# Candunio.net
KiCad netlist of a schematic drawn in Altium Designer
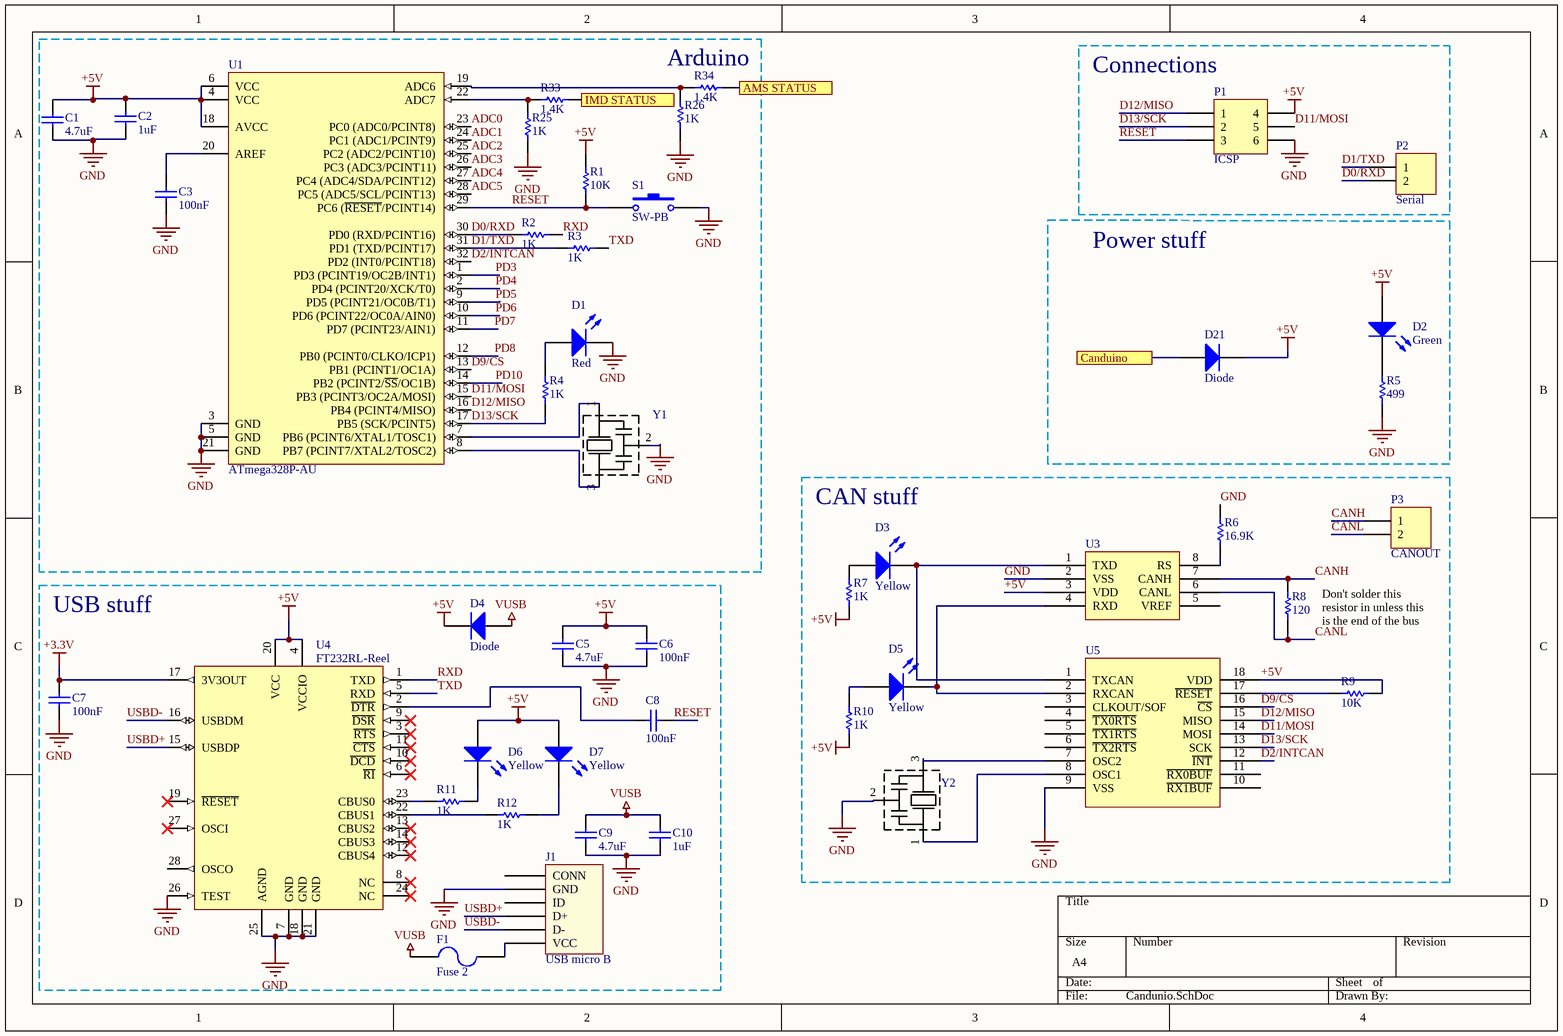
[diagram p0: Candunio.SchDoc]

(export (version "E")
  (design (tool "Eeschema 10.0.6"))
  (components
    (comp (ref "C1")
      (value "4.7uF")
      (footprint "CAPC3216X170N")
      (description "Capacitor (Semiconductor SIM Model)")
      (fields
        (field (name "MANUFACTURER") "Murata")
        (field (name "MANUFACTURER PART NUMBER") "GRM31MR71H105KA88L")
        (field (name "PUBLISHER") "Altium Limited")
      )
      (libsource (lib "PowerDistLib") (part "Cap Semi"))
    )
    (comp (ref "C2")
      (value "1uF")
      (footprint "CAPC3216X170N")
      (description "Capacitor (Semiconductor SIM Model)")
      (fields
        (field (name "MANUFACTURER") "Murata")
        (field (name "MANUFACTURER PART NUMBER") "GRM31MR71H105KA88L")
        (field (name "PUBLISHER") "Altium Limited")
      )
      (libsource (lib "PowerDistLib") (part "Cap Semi"))
    )
    (comp (ref "C3")
      (value "100nF")
      (footprint "CAPC3216X170N")
      (description "Capacitor (Semiconductor SIM Model)")
      (fields
        (field (name "MANUFACTURER") "Murata")
        (field (name "MANUFACTURER PART NUMBER") "GRM31MR71H105KA88L")
        (field (name "PUBLISHER") "Altium Limited")
      )
      (libsource (lib "PowerDistLib") (part "Cap Semi"))
    )
    (comp (ref "C5")
      (value "4.7uF")
      (footprint "PowerDistLib:CAPC3216X170N")
      (description "Capacitor (Semiconductor SIM Model)")
      (fields
        (field (name "MANUFACTURER") "Murata")
        (field (name "MANUFACTURER PART NUMBER") "GRM31MR71H105KA88L")
        (field (name "PUBLISHER") "Altium Limited")
      )
      (libsource (lib "PowerDistLib") (part "Cap Semi"))
    )
    (comp (ref "C6")
      (value "100nF")
      (footprint "CAPC3216X170N")
      (description "Capacitor (Semiconductor SIM Model)")
      (fields
        (field (name "MANUFACTURER") "Murata")
        (field (name "MANUFACTURER PART NUMBER") "GRM31MR71H105KA88L")
        (field (name "PUBLISHER") "Altium Limited")
      )
      (libsource (lib "PowerDistLib") (part "Cap Semi"))
    )
    (comp (ref "C7")
      (value "100nF")
      (footprint "PowerDistLib:CAPC3216X170N")
      (description "Capacitor (Semiconductor SIM Model)")
      (fields
        (field (name "MANUFACTURER") "Murata")
        (field (name "MANUFACTURER PART NUMBER") "GRM31MR71H105KA88L")
        (field (name "PUBLISHER") "Altium Limited")
      )
      (libsource (lib "PowerDistLib") (part "Cap Semi"))
    )
    (comp (ref "C8")
      (value "100nF")
      (footprint "CAPC3216X170N")
      (description "Capacitor (Semiconductor SIM Model)")
      (fields
        (field (name "MANUFACTURER") "Murata")
        (field (name "MANUFACTURER PART NUMBER") "GRM31MR71H105KA88L")
        (field (name "PUBLISHER") "Altium Limited")
      )
      (libsource (lib "PowerDistLib") (part "Cap Semi"))
    )
    (comp (ref "C9")
      (value "4.7uF")
      (footprint "CAPC3216X170N")
      (description "Capacitor (Semiconductor SIM Model)")
      (fields
        (field (name "MANUFACTURER") "Murata")
        (field (name "MANUFACTURER PART NUMBER") "GRM31MR71H105KA88L")
        (field (name "PUBLISHER") "Altium Limited")
      )
      (libsource (lib "PowerDistLib") (part "Cap Semi"))
    )
    (comp (ref "C10")
      (value "1uF")
      (footprint "CAPC3216X170N")
      (description "Capacitor (Semiconductor SIM Model)")
      (fields
        (field (name "MANUFACTURER") "Murata")
        (field (name "MANUFACTURER PART NUMBER") "GRM31MR71H105KA88L")
        (field (name "PUBLISHER") "Altium Limited")
      )
      (libsource (lib "PowerDistLib") (part "Cap Semi"))
    )
    (comp (ref "D1")
      (value "Red")
      (footprint "LEDC3216X120NRED")
      (description "Typical RED, GREEN, YELLOW, AMBER GaAs LED")
      (fields
        (field (name "MANUFACTURER") "Broadcom Avago")
        (field (name "MANUFACTURER PART NUMBER") "HSMY-C150")
        (field (name "PUBLISHER") "Altium Limited")
      )
      (libsource (lib "Miscellaneous Devices") (part "LED2"))
    )
    (comp (ref "D2")
      (value "Green")
      (footprint "LEDC3216X120NGRN")
      (description "Typical RED, GREEN, YELLOW, AMBER GaAs LED")
      (fields
        (field (name "MANUFACTURER") "Broadcom Avago")
        (field (name "MANUFACTURER PART NUMBER") "HSMG-C150")
        (field (name "PUBLISHER") "Altium Limited")
      )
      (libsource (lib "Miscellaneous Devices") (part "LED2"))
    )
    (comp (ref "D3")
      (value "Yellow")
      (footprint "LEDC3216X120NYEL")
      (description "Typical RED, GREEN, YELLOW, AMBER GaAs LED")
      (fields
        (field (name "MANUFACTURER") "Broadcom Avago")
        (field (name "MANUFACTURER PART NUMBER") "HSMY-C150")
        (field (name "PUBLISHER") "Altium Limited")
      )
      (libsource (lib "Miscellaneous Devices") (part "LED2"))
    )
    (comp (ref "D4")
      (value "Diode")
      (footprint "PowerDistLib:DO-220AA")
      (description "Default Diode")
      (fields (field (name "PUBLISHER") "Altium Limited"))
      (libsource (lib "PowerDistLib") (part "Diode"))
    )
    (comp (ref "D5")
      (value "Yellow")
      (footprint "LEDC3216X120NYEL")
      (description "Typical RED, GREEN, YELLOW, AMBER GaAs LED")
      (fields
        (field (name "MANUFACTURER") "Broadcom Avago")
        (field (name "MANUFACTURER PART NUMBER") "HSMY-C150")
        (field (name "PUBLISHER") "Altium Limited")
      )
      (libsource (lib "Miscellaneous Devices") (part "LED2"))
    )
    (comp (ref "D6")
      (value "Yellow")
      (footprint "LEDC3216X120NYEL")
      (description "Typical RED, GREEN, YELLOW, AMBER GaAs LED")
      (fields
        (field (name "MANUFACTURER") "Broadcom Avago")
        (field (name "MANUFACTURER PART NUMBER") "HSMY-C150")
        (field (name "PUBLISHER") "Altium Limited")
      )
      (libsource (lib "Miscellaneous Devices") (part "LED2"))
    )
    (comp (ref "D7")
      (value "Yellow")
      (footprint "LEDC3216X120NYEL")
      (description "Typical RED, GREEN, YELLOW, AMBER GaAs LED")
      (fields
        (field (name "MANUFACTURER") "Broadcom Avago")
        (field (name "MANUFACTURER PART NUMBER") "HSMY-C150")
        (field (name "PUBLISHER") "Altium Limited")
      )
      (libsource (lib "Miscellaneous Devices") (part "LED2"))
    )
    (comp (ref "D21")
      (value "Diode")
      (footprint "PowerDistLib:DO-220AA")
      (description "Default Diode")
      (fields (field (name "PUBLISHER") "Altium Limited"))
      (libsource (lib "PowerDistLib") (part "Diode"))
    )
    (comp (ref "F1")
      (value "Fuse 2")
      (footprint "1812")
      (description "Fuse")
      (fields
        (field (name "PART NUMBER") "MF-MSMF050-2")
        (field (name "MANUFACTURER") "Bourns")
        (field (name "PUBLISHER") "Altium Limited")
      )
      (libsource (lib "Miscellaneous Devices") (part "Fuse 2"))
    )
    (comp (ref "J1")
      (value "USB micro B")
      (footprint "1050170001")
      (description "CONN SM TH USB MICRO MODIFIED FOR DRILL")
      (fields (field (name "PART NUMBER") "WM1399CT-ND"))
      (libsource (lib "electronpowered") (part "1050170001"))
    )
    (comp (ref "P1")
      (value "ICSP")
      (footprint "Pin Header 2x3 TH Pitch 2.54mm")
      (description "Header, 3-Pin, Dual row")
      (fields (field (name "PUBLISHER") "Altium Limited"))
      (libsource (lib "PowerDistLib") (part "Header 3X2A"))
    )
    (comp (ref "P2")
      (value "Serial")
      (footprint "Pin Header 1x2 TH Pitch 2.54mm")
      (description "Header, 2-Pin")
      (fields (field (name "PUBLISHER") "Altium Limited"))
      (libsource (lib "Miscellaneous Connectors") (part "Header 2"))
    )
    (comp (ref "P3")
      (value "CANOUT")
      (description "Header, 2-Pin")
      (fields (field (name "PUBLISHER") "Altium Limited"))
      (libsource (lib "Miscellaneous Connectors") (part "Header 2"))
    )
    (comp (ref "R1")
      (value "10K")
      (footprint "RESC3216X60N")
      (description "Resistor")
      (fields
        (field (name "MANUFACTURER") "Stackpole Electronics")
        (field (name "MANUFACTURER PART NUMBER") "RNCP1206FTD1K00")
      )
      (libsource (lib "Miscellaneous Devices") (part "Res1"))
    )
    (comp (ref "R2")
      (value "1K")
      (footprint "RESC3216X60N")
      (description "Resistor")
      (fields
        (field (name "MANUFACTURER") "Stackpole Electronics")
        (field (name "MANUFACTURER PART NUMBER") "RNCP1206FTD1K00")
      )
      (libsource (lib "Miscellaneous Devices") (part "Res1"))
    )
    (comp (ref "R3")
      (value "1K")
      (footprint "RESC3216X60N")
      (description "Resistor")
      (fields
        (field (name "MANUFACTURER") "Stackpole Electronics")
        (field (name "MANUFACTURER PART NUMBER") "RNCP1206FTD1K00")
      )
      (libsource (lib "Miscellaneous Devices") (part "Res1"))
    )
    (comp (ref "R4")
      (value "1K")
      (footprint "RESC3216X60N")
      (description "Resistor")
      (fields
        (field (name "MANUFACTURER") "Stackpole Electronics")
        (field (name "MANUFACTURER PART NUMBER") "RNCP1206FTD1K00")
      )
      (libsource (lib "Miscellaneous Devices") (part "Res1"))
    )
    (comp (ref "R5")
      (value "499")
      (footprint "RESC3216X60N")
      (description "Resistor")
      (fields
        (field (name "MANUFACTURER") "Stackpole Electronics")
        (field (name "MANUFACTURER PART NUMBER") "RMCF1206FT499RCT-ND")
      )
      (libsource (lib "Miscellaneous Devices") (part "Res1"))
    )
    (comp (ref "R6")
      (value "16.9K")
      (footprint "RESC3216X60N")
      (description "Resistor")
      (fields
        (field (name "MANUFACTURER") "TE Connectivity Holsworthy")
        (field (name "MANUFACTURER PART NUMBER") "CRGH1206F16K9")
      )
      (libsource (lib "Miscellaneous Devices") (part "Res1"))
    )
    (comp (ref "R7")
      (value "1K")
      (footprint "RESC3216X60N")
      (description "Resistor")
      (fields
        (field (name "MANUFACTURER") "Stackpole Electronics")
        (field (name "MANUFACTURER PART NUMBER") "RNCP1206FTD1K00")
      )
      (libsource (lib "Miscellaneous Devices") (part "Res1"))
    )
    (comp (ref "R8")
      (value "120")
      (footprint "RESC3216X60N")
      (description "Resistor")
      (fields
        (field (name "MANUFACTURER") "Vishay")
        (field (name "MANUFACTURER PART NUMBER") "CRCW1206120RFKEAHP")
      )
      (libsource (lib "Miscellaneous Devices") (part "Res1"))
    )
    (comp (ref "R9")
      (value "10K")
      (footprint "RESC3216X60N")
      (description "Resistor")
      (fields
        (field (name "MANUFACTURER") "Stackpole Electronics")
        (field (name "MANUFACTURER PART NUMBER") "RNCP1206FTD10K0")
      )
      (libsource (lib "Miscellaneous Devices") (part "Res1"))
    )
    (comp (ref "R10")
      (value "1K")
      (footprint "RESC3216X60N")
      (description "Resistor")
      (fields
        (field (name "MANUFACTURER") "Stackpole Electronics")
        (field (name "MANUFACTURER PART NUMBER") "RNCP1206FTD1K00")
      )
      (libsource (lib "Miscellaneous Devices") (part "Res1"))
    )
    (comp (ref "R11")
      (value "1K")
      (footprint "RESC3216X60N")
      (description "Resistor")
      (fields
        (field (name "MANUFACTURER") "Stackpole Electronics")
        (field (name "MANUFACTURER PART NUMBER") "RNCP1206FTD1K00")
      )
      (libsource (lib "Miscellaneous Devices") (part "Res1"))
    )
    (comp (ref "R12")
      (value "1K")
      (footprint "RESC3216X60N")
      (description "Resistor")
      (fields
        (field (name "MANUFACTURER") "Stackpole Electronics")
        (field (name "MANUFACTURER PART NUMBER") "RNCP1206FTD1K00")
      )
      (libsource (lib "Miscellaneous Devices") (part "Res1"))
    )
    (comp (ref "R25")
      (value "1K")
      (footprint "RESC3216X60N")
      (description "Resistor")
      (fields
        (field (name "MANUFACTURER") "Stackpole Electronics")
        (field (name "MANUFACTURER PART NUMBER") "RNCP1206FTD1K00")
      )
      (libsource (lib "Power Distribution Unit 2019") (part "Res1"))
    )
    (comp (ref "R26")
      (value "1K")
      (footprint "RESC3216X60N")
      (description "Resistor")
      (fields
        (field (name "MANUFACTURER") "Stackpole Electronics")
        (field (name "MANUFACTURER PART NUMBER") "RNCP1206FTD1K00")
      )
      (libsource (lib "Power Distribution Unit 2019") (part "Res1"))
    )
    (comp (ref "R33")
      (value "1.4K")
      (footprint "RESC3216X60N")
      (description "Resistor")
      (fields
        (field (name "MANUFACTURER") "Stackpole Electronics")
        (field (name "MANUFACTURER PART NUMBER") "RNCP1206FTD1K00")
      )
      (libsource (lib "Power Distribution Unit 2019") (part "Res1"))
    )
    (comp (ref "R34")
      (value "1.4K")
      (footprint "RESC3216X60N")
      (description "Resistor")
      (fields
        (field (name "MANUFACTURER") "Stackpole Electronics")
        (field (name "MANUFACTURER PART NUMBER") "RNCP1206FTD1K00")
      )
      (libsource (lib "Power Distribution Unit 2019") (part "Res1"))
    )
    (comp (ref "S1")
      (value "SW-PB")
      (footprint "SMDswitch_1206")
      (description "Switch")
      (fields
        (field (name "MANUFACTURER") "ITT C&K")
        (field (name "MANUFACTURER PART NUMBER") "KXT331LHS")
        (field (name "PUBLISHER") "Altium Limited")
      )
      (libsource (lib "Miscellaneous Devices") (part "SW-PB"))
    )
    (comp (ref "U1")
      (value "ATmega328P-AU")
      (footprint "QFP80P900X900X120-32N")
      (fields (field (name "PUBLISHER") "Altium Limited"))
      (libsource (lib "Atmel Microcontroller 8-Bit megaAVR") (part "ATmega328P-AU"))
    )
    (comp (ref "U3")
      (value "MCP2551-E/SN")
      (footprint "SOIC127P600X175-8N")
      (description "SOIC")
      (libsource (lib "AMSComponents") (part "MCP2551-E/SN"))
    )
    (comp (ref "U4")
      (value "FT232RL-Reel")
      (footprint "PowerDist1:SOP65P780X200-28N")
      (description "USB UART Asynchronous Serial Data Transfer Chip, SSOP-28, Tape and Reel")
      (fields
        (field (name "MANUFACTURER") "FTDI")
        (field (name "MANUFACTURER PART NUMBER") "FT232RL-REEL")
        (field (name "PUBLISHER") "Altium Limited")
      )
      (libsource (lib "FTDI Communication UART") (part "FT232RL-Reel"))
    )
    (comp (ref "U5")
      (value "MCP2515-E/ST")
      (footprint "SOIC127P1030X265-18N")
      (description "SOIC")
      (libsource (lib "AMSComponents") (part "MCP2515-E/ST"))
    )
    (comp (ref "Y1")
      (value "CSTCE16M0V53-R0")
      (footprint "CSTCE_G")
      (fields
        (field (name "MANUFACTURER") "Murata")
        (field (name "MANUFACTURER PART NUMBER") "CSTCE16M0V53C-R0")
        (field (name "TOLERANCE") "0.5%")
      )
      (libsource (lib "AMSComponents") (part "CSTCE16M0V53-R0"))
    )
    (comp (ref "Y2")
      (value "CSTCE16M0V53-R0")
      (footprint "CSTCE_G")
      (fields
        (field (name "MANUFACTURER") "Murata")
        (field (name "MANUFACTURER PART NUMBER") "CSTCE16M0V53C-R0")
        (field (name "TOLERANCE") "0.5%")
      )
      (libsource (lib "AMSComponents") (part "CSTCE16M0V53-R0"))
    )
  )
  (nets
    (net (code "1") (name "+3.3V") (class "Default")
      (node (ref "C7") (pin "2") (pinfunction "2_2") (pintype "passive"))
      (node (ref "U4") (pin "17") (pinfunction "3V3OUT_17") (pintype "output"))
    )
    (net (code "2") (name "+5V") (class "Default")
      (node (ref "C1") (pin "1") (pinfunction "1_1") (pintype "passive"))
      (node (ref "C2") (pin "2") (pinfunction "2_2") (pintype "passive"))
      (node (ref "C5") (pin "2") (pinfunction "2_2") (pintype "passive"))
      (node (ref "C6") (pin "2") (pinfunction "2_2") (pintype "passive"))
      (node (ref "D2") (pin "1") (pinfunction "A_1") (pintype "passive"))
      (node (ref "D21") (pin "2") (pinfunction "K_2") (pintype "passive"))
      (node (ref "D4") (pin "2") (pinfunction "K_2") (pintype "passive"))
      (node (ref "D6") (pin "1") (pinfunction "A_1") (pintype "passive"))
      (node (ref "D7") (pin "1") (pinfunction "A_1") (pintype "passive"))
      (node (ref "P1") (pin "4") (pinfunction "4_4") (pintype "passive"))
      (node (ref "R1") (pin "1") (pinfunction "1_1") (pintype "passive"))
      (node (ref "R10") (pin "2") (pinfunction "2_2") (pintype "passive"))
      (node (ref "R7") (pin "1") (pinfunction "1_1") (pintype "passive"))
      (node (ref "R9") (pin "2") (pinfunction "2_2") (pintype "passive"))
      (node (ref "U1") (pin "18") (pinfunction "AVCC_18") (pintype "power_in"))
      (node (ref "U1") (pin "4") (pinfunction "VCC_4") (pintype "power_in"))
      (node (ref "U1") (pin "6") (pinfunction "VCC_6") (pintype "power_in"))
      (node (ref "U3") (pin "3") (pinfunction "VDD_3") (pintype "passive"))
      (node (ref "U4") (pin "20") (pinfunction "VCC_20") (pintype "power_in"))
      (node (ref "U4") (pin "4") (pinfunction "VCCIO_4") (pintype "power_in"))
      (node (ref "U5") (pin "18") (pinfunction "VDD_18") (pintype "passive"))
    )
    (net (code "3") (name "/ADC0") (class "Default")
      (node (ref "U1") (pin "23") (pinfunction "PC0_(ADC0/PCINT8)_23") (pintype "bidirectional"))
    )
    (net (code "4") (name "/ADC1") (class "Default")
      (node (ref "U1") (pin "24") (pinfunction "PC1_(ADC1/PCINT9)_24") (pintype "bidirectional"))
    )
    (net (code "5") (name "/ADC2") (class "Default")
      (node (ref "U1") (pin "25") (pinfunction "PC2_(ADC2/PCINT10)_25") (pintype "bidirectional"))
    )
    (net (code "6") (name "/ADC3") (class "Default")
      (node (ref "U1") (pin "26") (pinfunction "PC3_(ADC3/PCINT11)_26") (pintype "bidirectional"))
    )
    (net (code "7") (name "/ADC4") (class "Default")
      (node (ref "U1") (pin "27") (pinfunction "PC4_(ADC4/SDA/PCINT12)_27") (pintype "bidirectional"))
    )
    (net (code "8") (name "/ADC5") (class "Default")
      (node (ref "U1") (pin "28") (pinfunction "PC5_(ADC5/SCL/PCINT13)_28") (pintype "bidirectional"))
    )
    (net (code "9") (name "/AMS STATUS") (class "Default")
      (node (ref "R34") (pin "2") (pinfunction "2_2") (pintype "passive"))
    )
    (net (code "10") (name "/CANH") (class "Default")
      (node (ref "P3") (pin "1") (pinfunction "1_1") (pintype "passive"))
      (node (ref "R8") (pin "1") (pinfunction "1_1") (pintype "passive"))
      (node (ref "U3") (pin "7") (pinfunction "CANH_7") (pintype "passive"))
    )
    (net (code "11") (name "/CANL") (class "Default")
      (node (ref "P3") (pin "2") (pinfunction "2_2") (pintype "passive"))
      (node (ref "R8") (pin "2") (pinfunction "2_2") (pintype "passive"))
      (node (ref "U3") (pin "6") (pinfunction "CANL_6") (pintype "passive"))
    )
    (net (code "12") (name "/Canduino") (class "Default")
      (node (ref "D21") (pin "1") (pinfunction "A_1") (pintype "passive"))
    )
    (net (code "13") (name "/D0{slash}RXD") (class "Default")
      (node (ref "P2") (pin "2") (pinfunction "2_2") (pintype "passive"))
      (node (ref "R2") (pin "1") (pinfunction "1_1") (pintype "passive"))
      (node (ref "U1") (pin "30") (pinfunction "PD0_(RXD/PCINT16)_30") (pintype "bidirectional"))
    )
    (net (code "14") (name "/D1{slash}TXD") (class "Default")
      (node (ref "P2") (pin "1") (pinfunction "1_1") (pintype "passive"))
      (node (ref "R3") (pin "1") (pinfunction "1_1") (pintype "passive"))
      (node (ref "U1") (pin "31") (pinfunction "PD1_(TXD/PCINT17)_31") (pintype "bidirectional"))
    )
    (net (code "15") (name "/D2{slash}INTCAN") (class "Default")
      (node (ref "U1") (pin "32") (pinfunction "PD2_(INT0/PCINT18)_32") (pintype "bidirectional"))
      (node (ref "U5") (pin "12") (pinfunction "~{INT}_12") (pintype "passive"))
    )
    (net (code "16") (name "/D9{slash}CS") (class "Default")
      (node (ref "U1") (pin "13") (pinfunction "PB1_(PCINT1/OC1A)_13") (pintype "bidirectional"))
      (node (ref "U5") (pin "16") (pinfunction "~{CS}_16") (pintype "passive"))
    )
    (net (code "17") (name "/D11{slash}MOSI") (class "Default")
      (node (ref "P1") (pin "5") (pinfunction "5_5") (pintype "passive"))
      (node (ref "U1") (pin "15") (pinfunction "PB3_(PCINT3/OC2A/MOSI)_15") (pintype "bidirectional"))
      (node (ref "U5") (pin "14") (pinfunction "MOSI_14") (pintype "passive"))
    )
    (net (code "18") (name "/D12{slash}MISO") (class "Default")
      (node (ref "P1") (pin "1") (pinfunction "1_1") (pintype "passive"))
      (node (ref "U1") (pin "16") (pinfunction "PB4_(PCINT4/MISO)_16") (pintype "bidirectional"))
      (node (ref "U5") (pin "15") (pinfunction "MISO_15") (pintype "passive"))
    )
    (net (code "19") (name "/D13{slash}SCK") (class "Default")
      (node (ref "P1") (pin "2") (pinfunction "2_2") (pintype "passive"))
      (node (ref "R4") (pin "2") (pinfunction "2_2") (pintype "passive"))
      (node (ref "U1") (pin "17") (pinfunction "PB5_(SCK/PCINT5)_17") (pintype "bidirectional"))
      (node (ref "U5") (pin "13") (pinfunction "SCK_13") (pintype "passive"))
    )
    (net (code "20") (name "/IMD STATUS") (class "Default")
      (node (ref "R33") (pin "2") (pinfunction "2_2") (pintype "passive"))
    )
    (net (code "21") (name "/PD3") (class "Default")
      (node (ref "U1") (pin "1") (pinfunction "PD3_(PCINT19/OC2B/INT1)_1") (pintype "bidirectional"))
    )
    (net (code "22") (name "/PD4") (class "Default")
      (node (ref "U1") (pin "2") (pinfunction "PD4_(PCINT20/XCK/T0)_2") (pintype "bidirectional"))
    )
    (net (code "23") (name "/PD5") (class "Default")
      (node (ref "U1") (pin "9") (pinfunction "PD5_(PCINT21/OC0B/T1)_9") (pintype "bidirectional"))
    )
    (net (code "24") (name "/PD6") (class "Default")
      (node (ref "U1") (pin "10") (pinfunction "PD6_(PCINT22/OC0A/AIN0)_10") (pintype "bidirectional"))
    )
    (net (code "25") (name "/PD7") (class "Default")
      (node (ref "U1") (pin "11") (pinfunction "PD7_(PCINT23/AIN1)_11") (pintype "bidirectional"))
    )
    (net (code "26") (name "/PD8") (class "Default")
      (node (ref "U1") (pin "12") (pinfunction "PB0_(PCINT0/CLKO/ICP1)_12") (pintype "bidirectional"))
    )
    (net (code "27") (name "/PD10") (class "Default")
      (node (ref "U1") (pin "14") (pinfunction "PB2_(PCINT2/~{SS}/OC1B)_14") (pintype "bidirectional"))
    )
    (net (code "28") (name "/RESET") (class "Default")
      (node (ref "C8") (pin "2") (pinfunction "2_2") (pintype "passive"))
      (node (ref "P1") (pin "3") (pinfunction "3_3") (pintype "passive"))
      (node (ref "R1") (pin "2") (pinfunction "2_2") (pintype "passive"))
      (node (ref "S1") (pin "1") (pinfunction "1_1") (pintype "passive"))
      (node (ref "U1") (pin "29") (pinfunction "PC6_(~{RESET}/PCINT14)_29") (pintype "bidirectional"))
    )
    (net (code "29") (name "/RXD") (class "Default")
      (node (ref "R2") (pin "2") (pinfunction "2_2") (pintype "passive"))
      (node (ref "U4") (pin "1") (pinfunction "TXD_1") (pintype "output"))
    )
    (net (code "30") (name "/TXD") (class "Default")
      (node (ref "R3") (pin "2") (pinfunction "2_2") (pintype "passive"))
      (node (ref "U4") (pin "5") (pinfunction "RXD_5") (pintype "input"))
    )
    (net (code "31") (name "/USBD+") (class "Default")
      (node (ref "J1") (pin "3") (pinfunction "D+_3") (pintype "passive"))
      (node (ref "U4") (pin "15") (pinfunction "USBDP_15") (pintype "bidirectional"))
    )
    (net (code "32") (name "/USBD-") (class "Default")
      (node (ref "J1") (pin "2") (pinfunction "D-_2") (pintype "passive"))
      (node (ref "U4") (pin "16") (pinfunction "USBDM_16") (pintype "bidirectional"))
    )
    (net (code "33") (name "GND") (class "Default")
      (node (ref "C1") (pin "2") (pinfunction "2_2") (pintype "passive"))
      (node (ref "C10") (pin "1") (pinfunction "1_1") (pintype "passive"))
      (node (ref "C2") (pin "1") (pinfunction "1_1") (pintype "passive"))
      (node (ref "C3") (pin "1") (pinfunction "1_1") (pintype "passive"))
      (node (ref "C5") (pin "1") (pinfunction "1_1") (pintype "passive"))
      (node (ref "C6") (pin "1") (pinfunction "1_1") (pintype "passive"))
      (node (ref "C7") (pin "1") (pinfunction "1_1") (pintype "passive"))
      (node (ref "C9") (pin "1") (pinfunction "1_1") (pintype "passive"))
      (node (ref "D1") (pin "2") (pinfunction "K_2") (pintype "passive"))
      (node (ref "J1") (pin "5") (pinfunction "GND_5") (pintype "passive"))
      (node (ref "P1") (pin "6") (pinfunction "6_6") (pintype "passive"))
      (node (ref "R25") (pin "1") (pinfunction "1_1") (pintype "passive"))
      (node (ref "R26") (pin "1") (pinfunction "1_1") (pintype "passive"))
      (node (ref "R5") (pin "2") (pinfunction "2_2") (pintype "passive"))
      (node (ref "R6") (pin "1") (pinfunction "1_1") (pintype "passive"))
      (node (ref "S1") (pin "2") (pinfunction "2_2") (pintype "passive"))
      (node (ref "U1") (pin "21") (pinfunction "GND_21") (pintype "power_in"))
      (node (ref "U1") (pin "3") (pinfunction "GND_3") (pintype "power_in"))
      (node (ref "U1") (pin "5") (pinfunction "GND_5") (pintype "power_in"))
      (node (ref "U3") (pin "2") (pinfunction "VSS_2") (pintype "passive"))
      (node (ref "U4") (pin "18") (pinfunction "GND_18") (pintype "power_in"))
      (node (ref "U4") (pin "21") (pinfunction "GND_21") (pintype "power_in"))
      (node (ref "U4") (pin "25") (pinfunction "AGND_25") (pintype "power_in"))
      (node (ref "U4") (pin "26") (pinfunction "TEST_26") (pintype "input"))
      (node (ref "U4") (pin "7") (pinfunction "GND_7") (pintype "power_in"))
      (node (ref "U5") (pin "9") (pinfunction "VSS_9") (pintype "passive"))
      (node (ref "Y1") (pin "2") (pinfunction "2_2") (pintype "passive"))
      (node (ref "Y2") (pin "2") (pinfunction "2_2") (pintype "passive"))
    )
    (net (code "34") (name "Net-(D1-A)") (class "Default")
      (node (ref "D1") (pin "1") (pinfunction "A_1") (pintype "passive"))
      (node (ref "R4") (pin "1") (pinfunction "1_1") (pintype "passive"))
    )
    (net (code "35") (name "Net-(D2-K)") (class "Default")
      (node (ref "D2") (pin "2") (pinfunction "K_2") (pintype "passive"))
      (node (ref "R5") (pin "1") (pinfunction "1_1") (pintype "passive"))
    )
    (net (code "36") (name "Net-(D3-A)") (class "Default")
      (node (ref "D3") (pin "1") (pinfunction "A_1") (pintype "passive"))
      (node (ref "R7") (pin "2") (pinfunction "2_2") (pintype "passive"))
    )
    (net (code "37") (name "Net-(D3-K)") (class "Default")
      (node (ref "D3") (pin "2") (pinfunction "K_2") (pintype "passive"))
      (node (ref "U3") (pin "1") (pinfunction "TXD_1") (pintype "passive"))
      (node (ref "U5") (pin "1") (pinfunction "TXCAN_1") (pintype "passive"))
    )
    (net (code "38") (name "Net-(D5-A)") (class "Default")
      (node (ref "D5") (pin "1") (pinfunction "A_1") (pintype "passive"))
      (node (ref "R10") (pin "1") (pinfunction "1_1") (pintype "passive"))
    )
    (net (code "39") (name "Net-(D5-K)") (class "Default")
      (node (ref "D5") (pin "2") (pinfunction "K_2") (pintype "passive"))
      (node (ref "U3") (pin "4") (pinfunction "RXD_4") (pintype "passive"))
      (node (ref "U5") (pin "2") (pinfunction "RXCAN_2") (pintype "passive"))
    )
    (net (code "40") (name "Net-(D6-K)") (class "Default")
      (node (ref "D6") (pin "2") (pinfunction "K_2") (pintype "passive"))
      (node (ref "R11") (pin "2") (pinfunction "2_2") (pintype "passive"))
    )
    (net (code "41") (name "Net-(D7-K)") (class "Default")
      (node (ref "D7") (pin "2") (pinfunction "K_2") (pintype "passive"))
      (node (ref "R12") (pin "2") (pinfunction "2_2") (pintype "passive"))
    )
    (net (code "42") (name "Net-(J1-VCC)") (class "Default")
      (node (ref "F1") (pin "2") (pinfunction "2_2") (pintype "passive"))
      (node (ref "J1") (pin "1") (pinfunction "VCC_1") (pintype "passive"))
    )
    (net (code "43") (name "Net-(U1-ADC6)") (class "Default")
      (node (ref "R26") (pin "2") (pinfunction "2_2") (pintype "passive"))
      (node (ref "R34") (pin "1") (pinfunction "1_1") (pintype "passive"))
      (node (ref "U1") (pin "19") (pinfunction "ADC6_19") (pintype "input"))
    )
    (net (code "44") (name "Net-(U1-ADC7)") (class "Default")
      (node (ref "R25") (pin "2") (pinfunction "2_2") (pintype "passive"))
      (node (ref "R33") (pin "1") (pinfunction "1_1") (pintype "passive"))
      (node (ref "U1") (pin "22") (pinfunction "ADC7_22") (pintype "input"))
    )
    (net (code "45") (name "Net-(U1-AREF)") (class "Default")
      (node (ref "C3") (pin "2") (pinfunction "2_2") (pintype "passive"))
      (node (ref "U1") (pin "20") (pinfunction "AREF_20") (pintype "passive"))
    )
    (net (code "46") (name "Net-(U1-PB6_(PCINT6{slash}XTAL1{slash}TOSC1))") (class "Default")
      (node (ref "U1") (pin "7") (pinfunction "PB6_(PCINT6/XTAL1/TOSC1)_7") (pintype "bidirectional"))
      (node (ref "Y1") (pin "1") (pinfunction "1_1") (pintype "passive"))
    )
    (net (code "47") (name "Net-(U1-PB7_(PCINT7{slash}XTAL2{slash}TOSC2))") (class "Default")
      (node (ref "U1") (pin "8") (pinfunction "PB7_(PCINT7/XTAL2/TOSC2)_8") (pintype "bidirectional"))
      (node (ref "Y1") (pin "3") (pinfunction "3_3") (pintype "passive"))
    )
    (net (code "48") (name "Net-(U3-RS)") (class "Default")
      (node (ref "R6") (pin "2") (pinfunction "2_2") (pintype "passive"))
      (node (ref "U3") (pin "8") (pinfunction "RS_8") (pintype "passive"))
    )
    (net (code "49") (name "Net-(U4-CBUS0)") (class "Default")
      (node (ref "R11") (pin "1") (pinfunction "1_1") (pintype "passive"))
      (node (ref "U4") (pin "23") (pinfunction "CBUS0_23") (pintype "bidirectional"))
    )
    (net (code "50") (name "Net-(U4-CBUS1)") (class "Default")
      (node (ref "R12") (pin "1") (pinfunction "1_1") (pintype "passive"))
      (node (ref "U4") (pin "22") (pinfunction "CBUS1_22") (pintype "bidirectional"))
    )
    (net (code "51") (name "Net-(U4-~{DTR})") (class "Default")
      (node (ref "C8") (pin "1") (pinfunction "1_1") (pintype "passive"))
      (node (ref "U4") (pin "2") (pinfunction "~{DTR}_2") (pintype "output"))
    )
    (net (code "52") (name "Net-(U5-OSC1)") (class "Default")
      (node (ref "U5") (pin "8") (pinfunction "OSC1_8") (pintype "passive"))
      (node (ref "Y2") (pin "1") (pinfunction "1_1") (pintype "passive"))
    )
    (net (code "53") (name "Net-(U5-OSC2)") (class "Default")
      (node (ref "U5") (pin "7") (pinfunction "OSC2_7") (pintype "passive"))
      (node (ref "Y2") (pin "3") (pinfunction "3_3") (pintype "passive"))
    )
    (net (code "54") (name "Net-(U5-~{RESET})") (class "Default")
      (node (ref "R9") (pin "1") (pinfunction "1_1") (pintype "passive"))
      (node (ref "U5") (pin "17") (pinfunction "~{RESET}_17") (pintype "passive"))
    )
    (net (code "55") (name "VUSB") (class "Default")
      (node (ref "C10") (pin "2") (pinfunction "2_2") (pintype "passive"))
      (node (ref "C9") (pin "2") (pinfunction "2_2") (pintype "passive"))
      (node (ref "D4") (pin "1") (pinfunction "A_1") (pintype "passive"))
      (node (ref "F1") (pin "1") (pinfunction "1_1") (pintype "passive"))
    )
    (net (code "56") (name "unconnected-(J1-CONN-Pad0)") (class "Default")
      (node (ref "J1") (pin "0") (pinfunction "CONN_0") (pintype "passive"))
    )
    (net (code "57") (name "unconnected-(J1-ID-Pad4)") (class "Default")
      (node (ref "J1") (pin "4") (pinfunction "ID_4") (pintype "passive"))
    )
    (net (code "58") (name "unconnected-(U3-VREF-Pad5)") (class "Default")
      (node (ref "U3") (pin "5") (pinfunction "VREF_5") (pintype "passive"))
    )
    (net (code "59") (name "unconnected-(U4-CBUS2-Pad13)") (class "Default")
      (node (ref "U4") (pin "13") (pinfunction "CBUS2_13") (pintype "bidirectional+no_connect"))
    )
    (net (code "60") (name "unconnected-(U4-CBUS3-Pad14)") (class "Default")
      (node (ref "U4") (pin "14") (pinfunction "CBUS3_14") (pintype "bidirectional+no_connect"))
    )
    (net (code "61") (name "unconnected-(U4-CBUS4-Pad12)") (class "Default")
      (node (ref "U4") (pin "12") (pinfunction "CBUS4_12") (pintype "bidirectional+no_connect"))
    )
    (net (code "62") (name "unconnected-(U4-NC-Pad8)") (class "Default")
      (node (ref "U4") (pin "8") (pinfunction "NC_8") (pintype "passive+no_connect"))
    )
    (net (code "63") (name "unconnected-(U4-NC-Pad24)") (class "Default")
      (node (ref "U4") (pin "24") (pinfunction "NC_24") (pintype "passive+no_connect"))
    )
    (net (code "64") (name "unconnected-(U4-OSCI-Pad27)") (class "Default")
      (node (ref "U4") (pin "27") (pinfunction "OSCI_27") (pintype "input+no_connect"))
    )
    (net (code "65") (name "unconnected-(U4-OSCO-Pad28)") (class "Default")
      (node (ref "U4") (pin "28") (pinfunction "OSCO_28") (pintype "output"))
    )
    (net (code "66") (name "unconnected-(U4-~{CTS}-Pad11)") (class "Default")
      (node (ref "U4") (pin "11") (pinfunction "~{CTS}_11") (pintype "input+no_connect"))
    )
    (net (code "67") (name "unconnected-(U4-~{DCD}-Pad10)") (class "Default")
      (node (ref "U4") (pin "10") (pinfunction "~{DCD}_10") (pintype "input+no_connect"))
    )
    (net (code "68") (name "unconnected-(U4-~{DSR}-Pad9)") (class "Default")
      (node (ref "U4") (pin "9") (pinfunction "~{DSR}_9") (pintype "input+no_connect"))
    )
    (net (code "69") (name "unconnected-(U4-~{RESET}-Pad19)") (class "Default")
      (node (ref "U4") (pin "19") (pinfunction "~{RESET}_19") (pintype "input+no_connect"))
    )
    (net (code "70") (name "unconnected-(U4-~{RI}-Pad6)") (class "Default")
      (node (ref "U4") (pin "6") (pinfunction "~{RI}_6") (pintype "input+no_connect"))
    )
    (net (code "71") (name "unconnected-(U4-~{RTS}-Pad3)") (class "Default")
      (node (ref "U4") (pin "3") (pinfunction "~{RTS}_3") (pintype "output+no_connect"))
    )
    (net (code "72") (name "unconnected-(U5-CLKOUT{slash}SOF-Pad3)") (class "Default")
      (node (ref "U5") (pin "3") (pinfunction "CLKOUT/SOF_3") (pintype "passive"))
    )
    (net (code "73") (name "unconnected-(U5-~{RX0BUF}-Pad11)") (class "Default")
      (node (ref "U5") (pin "11") (pinfunction "~{RX0BUF}_11") (pintype "passive"))
    )
    (net (code "74") (name "unconnected-(U5-~{RX1BUF}-Pad10)") (class "Default")
      (node (ref "U5") (pin "10") (pinfunction "~{RX1BUF}_10") (pintype "passive"))
    )
    (net (code "75") (name "unconnected-(U5-~{TX0RTS}-Pad4)") (class "Default")
      (node (ref "U5") (pin "4") (pinfunction "~{TX0RTS}_4") (pintype "passive"))
    )
    (net (code "76") (name "unconnected-(U5-~{TX1RTS}-Pad5)") (class "Default")
      (node (ref "U5") (pin "5") (pinfunction "~{TX1RTS}_5") (pintype "passive"))
    )
    (net (code "77") (name "unconnected-(U5-~{TX2RTS}-Pad6)") (class "Default")
      (node (ref "U5") (pin "6") (pinfunction "~{TX2RTS}_6") (pintype "passive"))
    )
  )
)
